# GB202-CC-Modem.net
KiCad netlist of a schematic drawn in EAGLE
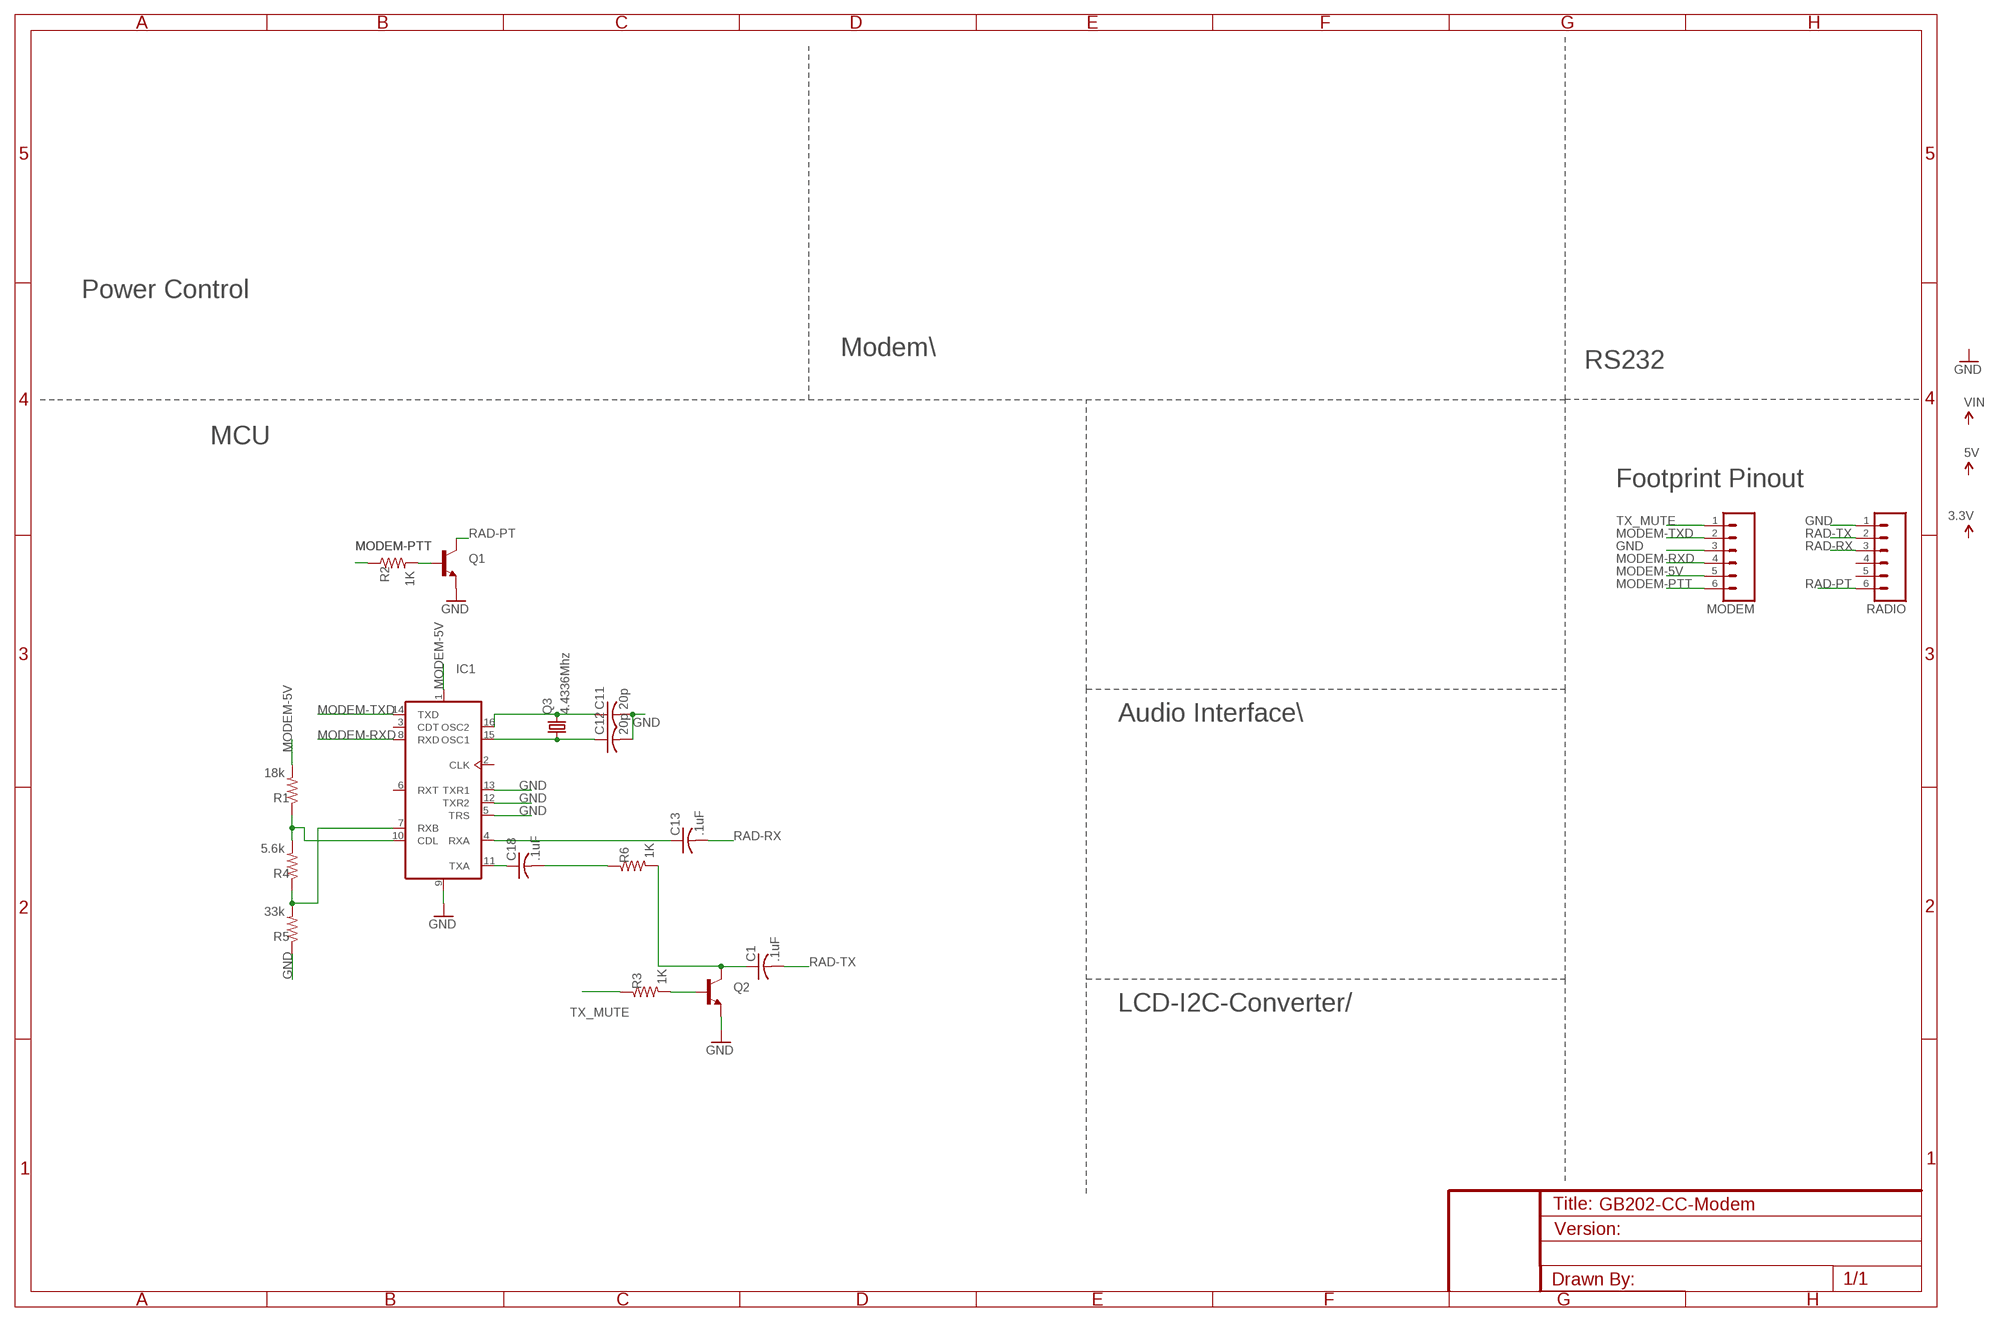
[diagram p0: schematic, sheet 1]

(export (version "E")
  (design (tool "Eeschema 10.0.6"))
  (components
    (comp (ref "C1")
      (value ".1uF")
      (footprint "eagle-import:C050-024X044")
      (libsource (lib "eagle-import") (part "C-US050-024X044"))
    )
    (comp (ref "C11")
      (value "20p")
      (footprint "eagle-import:C0603")
      (libsource (lib "eagle-import") (part "C-USC0603"))
    )
    (comp (ref "C12")
      (value "20p")
      (footprint "eagle-import:C0603")
      (libsource (lib "eagle-import") (part "C-USC0603"))
    )
    (comp (ref "C13")
      (value ".1uF")
      (footprint "eagle-import:C050-024X044")
      (libsource (lib "eagle-import") (part "C-US050-024X044"))
    )
    (comp (ref "C18")
      (value ".1uF")
      (footprint "eagle-import:C050-024X044")
      (libsource (lib "eagle-import") (part "C-US050-024X044"))
    )
    (comp (ref "IC1")
      (value "TCM3105")
      (footprint "eagle-import:DIL16")
      (libsource (lib "eagle-import") (part "TCM3105"))
    )
    (comp (ref "MODEM")
      (value "M06LONGPADS")
      (footprint "eagle-import:1X06_LONGPADS")
      (libsource (lib "eagle-import") (part "M06LONGPADS"))
    )
    (comp (ref "Q1")
      (value "TRANSISTOR_NPNP2N2222A")
      (footprint "eagle-import:TO-92")
      (libsource (lib "eagle-import") (part "TRANSISTOR_NPNP2N2222A"))
    )
    (comp (ref "Q2")
      (value "TRANSISTOR_NPN2N3904")
      (footprint "eagle-import:TO-92")
      (libsource (lib "eagle-import") (part "TRANSISTOR_NPN2N3904"))
    )
    (comp (ref "Q3")
      (value "4.4336Mhz")
      (footprint "eagle-import:HC49_S")
      (libsource (lib "eagle-import") (part "CRYSTALHC49S"))
    )
    (comp (ref "R1")
      (value "18k")
      (footprint "eagle-import:AXIAL-0.3")
      (libsource (lib "eagle-import") (part "RESISTORAXIAL-0.3"))
    )
    (comp (ref "R2")
      (value "1K")
      (footprint "eagle-import:AXIAL-0.3")
      (libsource (lib "eagle-import") (part "RESISTORAXIAL-0.3"))
    )
    (comp (ref "R3")
      (value "1K")
      (footprint "eagle-import:AXIAL-0.3")
      (libsource (lib "eagle-import") (part "RESISTORAXIAL-0.3"))
    )
    (comp (ref "R4")
      (value "5.6k")
      (footprint "eagle-import:AXIAL-0.3")
      (libsource (lib "eagle-import") (part "RESISTORAXIAL-0.3"))
    )
    (comp (ref "R5")
      (value "33k")
      (footprint "eagle-import:AXIAL-0.3-KIT")
      (libsource (lib "eagle-import") (part "RESISTORKIT"))
    )
    (comp (ref "R6")
      (value "1K")
      (footprint "eagle-import:AXIAL-0.3")
      (libsource (lib "eagle-import") (part "RESISTORAXIAL-0.3"))
    )
    (comp (ref "RADIO")
      (value "M06LONGPADS")
      (footprint "eagle-import:1X06_LONGPADS")
      (libsource (lib "eagle-import") (part "M06LONGPADS"))
    )
  )
  (nets
    (net (code "1") (name "/MODEM-5V") (class "Default")
      (node (ref "IC1") (pin "1") (pinfunction "VDD_1") (pintype "power_in"))
      (node (ref "MODEM") (pin "5") (pinfunction "5_5") (pintype "passive"))
      (node (ref "R1") (pin "P$2") (pinfunction "2_P$2") (pintype "passive"))
    )
    (net (code "2") (name "/MODEM-PTT") (class "Default")
      (node (ref "MODEM") (pin "6") (pinfunction "6_6") (pintype "passive"))
      (node (ref "R2") (pin "P$1") (pinfunction "1_P$1") (pintype "passive"))
    )
    (net (code "3") (name "/MODEM-RXD") (class "Default")
      (node (ref "IC1") (pin "8") (pinfunction "RXD_8") (pintype "output"))
      (node (ref "MODEM") (pin "4") (pinfunction "4_4") (pintype "passive"))
    )
    (net (code "4") (name "/MODEM-TXD") (class "Default")
      (node (ref "IC1") (pin "14") (pinfunction "TXD_14") (pintype "input"))
      (node (ref "MODEM") (pin "2") (pinfunction "2_2") (pintype "passive"))
    )
    (net (code "5") (name "/RAD-PT") (class "Default")
      (node (ref "Q1") (pin "1") (pinfunction "C_1") (pintype "passive"))
      (node (ref "RADIO") (pin "6") (pinfunction "6_6") (pintype "passive"))
    )
    (net (code "6") (name "/RAD-RX") (class "Default")
      (node (ref "C13") (pin "2") (pinfunction "2_2") (pintype "passive"))
      (node (ref "RADIO") (pin "3") (pinfunction "3_3") (pintype "passive"))
    )
    (net (code "7") (name "/RAD-TX") (class "Default")
      (node (ref "C1") (pin "2") (pinfunction "2_2") (pintype "passive"))
      (node (ref "RADIO") (pin "2") (pinfunction "2_2") (pintype "passive"))
    )
    (net (code "8") (name "/TX_MUTE") (class "Default")
      (node (ref "MODEM") (pin "1") (pinfunction "1_1") (pintype "passive"))
      (node (ref "R3") (pin "P$1") (pinfunction "1_P$1") (pintype "passive"))
    )
    (net (code "11") (name "GND") (class "Default")
      (node (ref "C11") (pin "2") (pinfunction "2_2") (pintype "passive"))
      (node (ref "C12") (pin "2") (pinfunction "2_2") (pintype "passive"))
      (node (ref "IC1") (pin "12") (pinfunction "TXR2_12") (pintype "input"))
      (node (ref "IC1") (pin "13") (pinfunction "TXR1_13") (pintype "input"))
      (node (ref "IC1") (pin "5") (pinfunction "TRS_5") (pintype "input"))
      (node (ref "IC1") (pin "9") (pinfunction "VSS_9") (pintype "power_in"))
      (node (ref "MODEM") (pin "3") (pinfunction "3_3") (pintype "passive"))
      (node (ref "Q1") (pin "3") (pinfunction "E_3") (pintype "passive"))
      (node (ref "Q2") (pin "1") (pinfunction "E_1") (pintype "passive"))
      (node (ref "R5") (pin "P$1") (pinfunction "1_P$1") (pintype "passive"))
      (node (ref "RADIO") (pin "1") (pinfunction "1_1") (pintype "passive"))
    )
    (net (code "12") (name "Net-(IC1-CDL)") (class "Default")
      (node (ref "IC1") (pin "10") (pinfunction "CDL_10") (pintype "bidirectional"))
      (node (ref "R1") (pin "P$1") (pinfunction "1_P$1") (pintype "passive"))
      (node (ref "R4") (pin "P$2") (pinfunction "2_P$2") (pintype "passive"))
    )
    (net (code "13") (name "Net-(IC1-OSC1)") (class "Default")
      (node (ref "C12") (pin "1") (pinfunction "1_1") (pintype "passive"))
      (node (ref "IC1") (pin "15") (pinfunction "OSC1_15") (pintype "bidirectional"))
      (node (ref "Q3") (pin "1") (pinfunction "1_1") (pintype "passive"))
    )
    (net (code "14") (name "Net-(IC1-OSC2)") (class "Default")
      (node (ref "C11") (pin "1") (pinfunction "1_1") (pintype "passive"))
      (node (ref "IC1") (pin "16") (pinfunction "OSC2_16") (pintype "bidirectional"))
      (node (ref "Q3") (pin "2") (pinfunction "2_2") (pintype "passive"))
    )
    (net (code "15") (name "Net-(IC1-RXA)") (class "Default")
      (node (ref "C13") (pin "1") (pinfunction "1_1") (pintype "passive"))
      (node (ref "IC1") (pin "4") (pinfunction "RXA_4") (pintype "input"))
    )
    (net (code "16") (name "Net-(IC1-RXB)") (class "Default")
      (node (ref "IC1") (pin "7") (pinfunction "RXB_7") (pintype "bidirectional"))
      (node (ref "R4") (pin "P$1") (pinfunction "1_P$1") (pintype "passive"))
      (node (ref "R5") (pin "P$2") (pinfunction "2_P$2") (pintype "passive"))
    )
    (net (code "17") (name "Net-(IC1-TXA)") (class "Default")
      (node (ref "C18") (pin "1") (pinfunction "1_1") (pintype "passive"))
      (node (ref "IC1") (pin "11") (pinfunction "TXA_11") (pintype "output"))
    )
    (net (code "18") (name "Net-(Q1-B)") (class "Default")
      (node (ref "Q1") (pin "2") (pinfunction "B_2") (pintype "passive"))
      (node (ref "R2") (pin "P$2") (pinfunction "2_P$2") (pintype "passive"))
    )
    (net (code "19") (name "Net-(Q2-B)") (class "Default")
      (node (ref "Q2") (pin "2") (pinfunction "B_2") (pintype "passive"))
      (node (ref "R3") (pin "P$2") (pinfunction "2_P$2") (pintype "passive"))
    )
    (net (code "20") (name "Net-(Q2-C)") (class "Default")
      (node (ref "C1") (pin "1") (pinfunction "1_1") (pintype "passive"))
      (node (ref "Q2") (pin "3") (pinfunction "C_3") (pintype "passive"))
      (node (ref "R6") (pin "P$2") (pinfunction "2_P$2") (pintype "passive"))
    )
    (net (code "21") (name "Net-(R6-1)") (class "Default")
      (node (ref "C18") (pin "2") (pinfunction "2_2") (pintype "passive"))
      (node (ref "R6") (pin "P$1") (pinfunction "1_P$1") (pintype "passive"))
    )
    (net (code "23") (name "unconnected-(IC1-CDT-Pad3)") (class "Default")
      (node (ref "IC1") (pin "3") (pinfunction "CDT_3") (pintype "output"))
    )
    (net (code "24") (name "unconnected-(IC1-CLK-Pad2)") (class "Default")
      (node (ref "IC1") (pin "2") (pinfunction "CLK_2") (pintype "output"))
    )
    (net (code "25") (name "unconnected-(IC1-RXT-Pad6)") (class "Default")
      (node (ref "IC1") (pin "6") (pinfunction "RXT_6") (pintype "bidirectional"))
    )
    (net (code "26") (name "unconnected-(RADIO-Pad4)") (class "Default")
      (node (ref "RADIO") (pin "4") (pinfunction "4_4") (pintype "passive"))
    )
    (net (code "27") (name "unconnected-(RADIO-Pad5)") (class "Default")
      (node (ref "RADIO") (pin "5") (pinfunction "5_5") (pintype "passive"))
    )
  )
)
